# alimentacion.net
KiCad netlist of a schematic drawn in Altium Designer
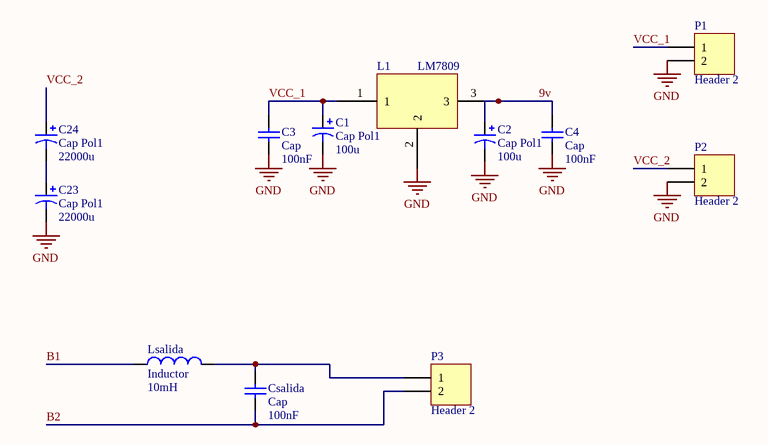
[diagram p0: alimentacion.SchDoc]

(export (version "E")
  (design (tool "Eeschema 10.0.6"))
  (components
    (comp (ref "C1")
      (value "Cap Pol1")
      (footprint "A")
      (description "Polarized Capacitor (Radial)")
      (fields (field (name "ALTIUM_VALUE") "100u") (field (name "PUBLISHER") "Altium Limited"))
      (libsource (lib "Miscellaneous Devices") (part "Cap Pol1"))
    )
    (comp (ref "C2")
      (value "Cap Pol1")
      (footprint "A")
      (description "Polarized Capacitor (Radial)")
      (fields (field (name "ALTIUM_VALUE") "100u") (field (name "PUBLISHER") "Altium Limited"))
      (libsource (lib "Miscellaneous Devices") (part "Cap Pol1"))
    )
    (comp (ref "C3")
      (value "Cap")
      (footprint "C1206")
      (description "Capacitor")
      (fields (field (name "ALTIUM_VALUE") "100nF") (field (name "PUBLISHER") "Altium Limited"))
      (libsource (lib "Miscellaneous Devices") (part "Cap"))
    )
    (comp (ref "C4")
      (value "Cap")
      (footprint "C1206")
      (description "Capacitor")
      (fields (field (name "ALTIUM_VALUE") "100nF") (field (name "PUBLISHER") "Altium Limited"))
      (libsource (lib "Miscellaneous Devices") (part "Cap"))
    )
    (comp (ref "C23")
      (value "Cap Pol1")
      (footprint "Capacitor gigante")
      (description "Polarized Capacitor (Radial)")
      (fields (field (name "ALTIUM_VALUE") "22000u") (field (name "PUBLISHER") "Altium Limited"))
      (libsource (lib "Miscellaneous Devices") (part "Cap Pol1"))
    )
    (comp (ref "C24")
      (value "Cap Pol1")
      (footprint "Capacitor gigante")
      (description "Polarized Capacitor (Radial)")
      (fields (field (name "ALTIUM_VALUE") "22000u") (field (name "PUBLISHER") "Altium Limited"))
      (libsource (lib "Miscellaneous Devices") (part "Cap Pol1"))
    )
    (comp (ref "Csalida")
      (value "Cap")
      (footprint "A")
      (description "Capacitor")
      (fields (field (name "ALTIUM_VALUE") "100nF") (field (name "PUBLISHER") "Altium Limited"))
      (libsource (lib "Miscellaneous Devices") (part "Cap"))
    )
    (comp (ref "L1") (value "LM7809") (footprint "TO-220AB") (libsource (lib "LM7809") (part "LM7809")))
    (comp (ref "Lsalida")
      (value "Inductor")
      (footprint "A")
      (fields (field (name "ALTIUM_VALUE") "10mH") (field (name "PUBLISHER") "Altium Limited"))
      (libsource (lib "Miscellaneous Devices") (part "Inductor"))
    )
    (comp (ref "P1")
      (value "Header 2")
      (footprint "HDR1X2")
      (description "Header, 2-Pin")
      (fields (field (name "PUBLISHER") "Altium Limited"))
      (libsource (lib "Miscellaneous Connectors") (part "Header 2"))
    )
    (comp (ref "P2")
      (value "Header 2")
      (footprint "HDR1X2")
      (description "Header, 2-Pin")
      (fields (field (name "PUBLISHER") "Altium Limited"))
      (libsource (lib "Miscellaneous Connectors") (part "Header 2"))
    )
    (comp (ref "P3")
      (value "Header 2")
      (footprint "HDR1X2")
      (description "Header, 2-Pin")
      (fields (field (name "PUBLISHER") "Altium Limited"))
      (libsource (lib "Miscellaneous Connectors") (part "Header 2"))
    )
  )
  (nets
    (net (code "1") (name "/9v") (class "Default")
      (node (ref "C2") (pin "1") (pinfunction "1_1") (pintype "passive"))
      (node (ref "C4") (pin "2") (pinfunction "2_2") (pintype "passive"))
      (node (ref "L1") (pin "3") (pinfunction "3_3") (pintype "passive"))
    )
    (net (code "2") (name "/B1") (class "Default")
      (node (ref "Lsalida") (pin "1") (pinfunction "1_1") (pintype "passive"))
    )
    (net (code "3") (name "/B2") (class "Default")
      (node (ref "Csalida") (pin "1") (pinfunction "1_1") (pintype "passive"))
      (node (ref "P3") (pin "2") (pinfunction "2_2") (pintype "passive"))
    )
    (net (code "4") (name "/VCC_1") (class "Default")
      (node (ref "C1") (pin "1") (pinfunction "1_1") (pintype "passive"))
      (node (ref "C3") (pin "2") (pinfunction "2_2") (pintype "passive"))
      (node (ref "L1") (pin "1") (pinfunction "1_1") (pintype "passive"))
      (node (ref "P1") (pin "1") (pinfunction "1_1") (pintype "passive"))
    )
    (net (code "5") (name "/VCC_2") (class "Default")
      (node (ref "C24") (pin "1") (pinfunction "1_1") (pintype "passive"))
      (node (ref "P2") (pin "1") (pinfunction "1_1") (pintype "passive"))
    )
    (net (code "6") (name "GND") (class "Default")
      (node (ref "C1") (pin "2") (pinfunction "2_2") (pintype "passive"))
      (node (ref "C2") (pin "2") (pinfunction "2_2") (pintype "passive"))
      (node (ref "C23") (pin "2") (pinfunction "2_2") (pintype "passive"))
      (node (ref "C3") (pin "1") (pinfunction "1_1") (pintype "passive"))
      (node (ref "C4") (pin "1") (pinfunction "1_1") (pintype "passive"))
      (node (ref "L1") (pin "2") (pinfunction "2_2") (pintype "passive"))
      (node (ref "P1") (pin "2") (pinfunction "2_2") (pintype "passive"))
      (node (ref "P2") (pin "2") (pinfunction "2_2") (pintype "passive"))
    )
    (net (code "7") (name "Net-(C23-Pad1)") (class "Default")
      (node (ref "C23") (pin "1") (pinfunction "1_1") (pintype "passive"))
      (node (ref "C24") (pin "2") (pinfunction "2_2") (pintype "passive"))
    )
    (net (code "8") (name "Net-(Csalida-Pad2)") (class "Default")
      (node (ref "Csalida") (pin "2") (pinfunction "2_2") (pintype "passive"))
      (node (ref "Lsalida") (pin "2") (pinfunction "2_2") (pintype "passive"))
      (node (ref "P3") (pin "1") (pinfunction "1_1") (pintype "passive"))
    )
  )
)
